# WS2812B_Ring_Light.net
KiCad netlist of a schematic drawn in Altium Designer
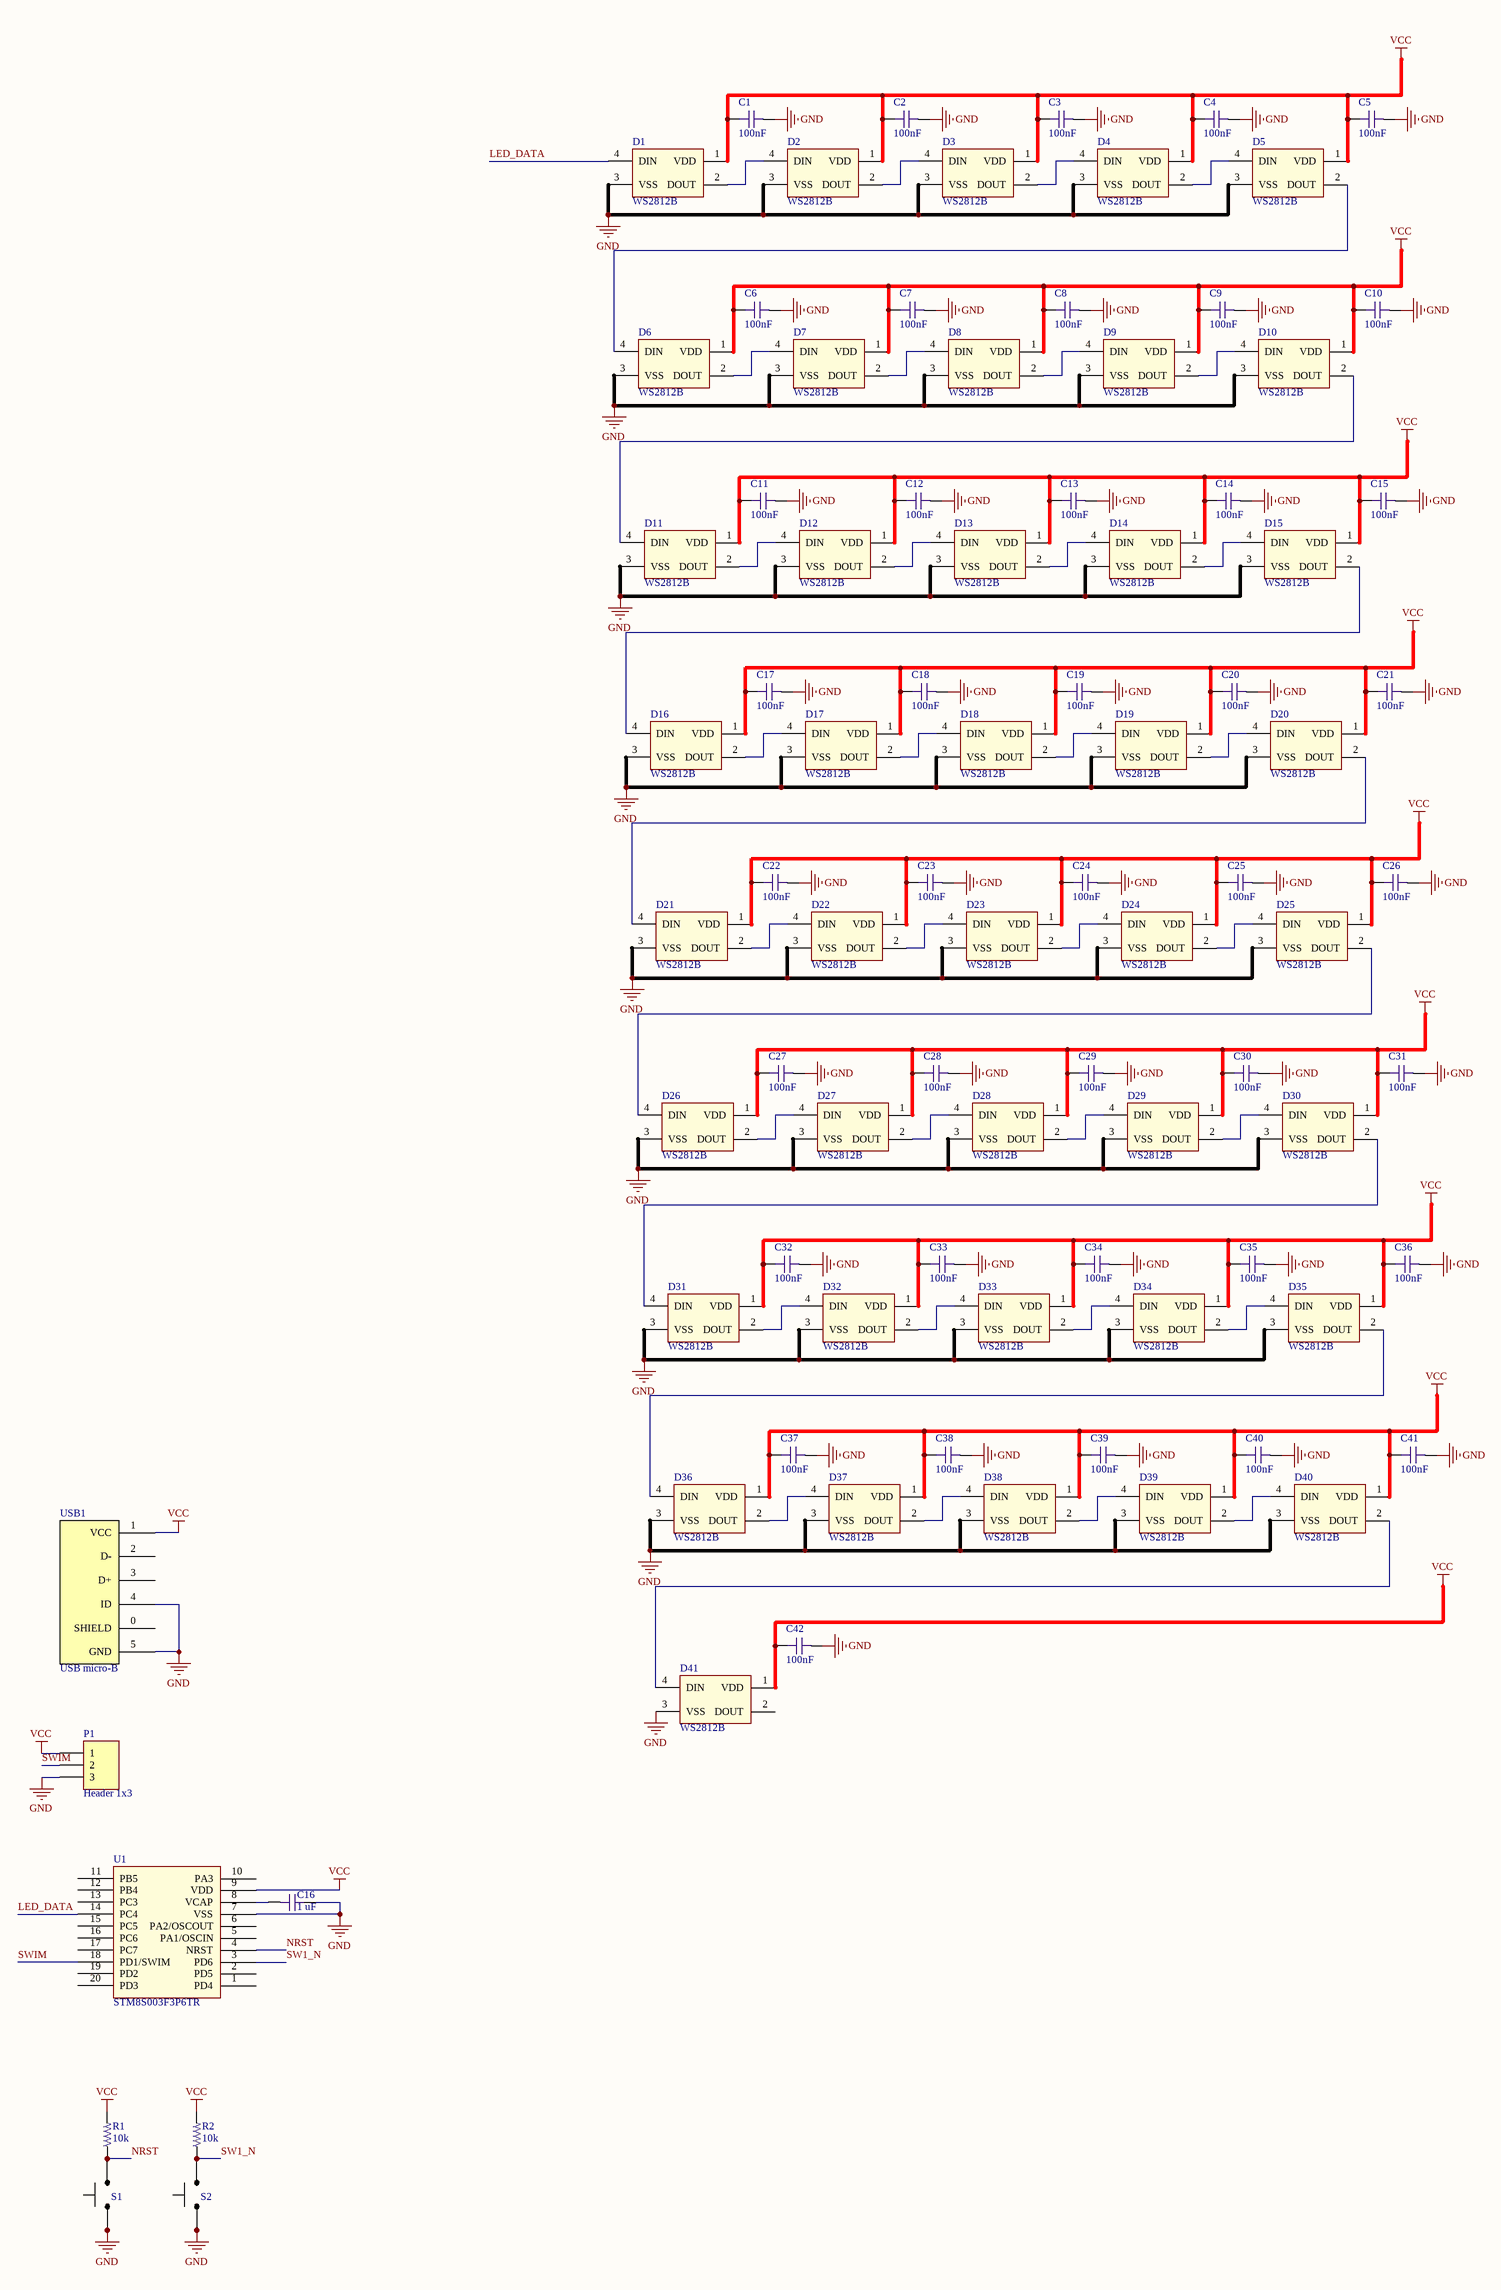
[diagram p0: WS2812B_Ring_Light.SchDoc]

(export (version "E")
  (design (tool "Eeschema 10.0.6"))
  (components
    (comp (ref "C1")
      (value "100nF")
      (footprint "C0603-IPC")
      (description "Chip Capacitor, 0603, 100nF, 25V, X7R")
      (fields (field (name "Comment") "C0603 100nF 25V X7R"))
      (libsource (lib "Capacitors") (part "C0603 100nF 25V X7R"))
    )
    (comp (ref "C2")
      (value "100nF")
      (footprint "C0603-IPC")
      (description "Chip Capacitor, 0603, 100nF, 25V, X7R")
      (fields (field (name "Comment") "C0603 100nF 25V X7R"))
      (libsource (lib "Capacitors") (part "C0603 100nF 25V X7R"))
    )
    (comp (ref "C3")
      (value "100nF")
      (footprint "C0603-IPC")
      (description "Chip Capacitor, 0603, 100nF, 25V, X7R")
      (fields (field (name "Comment") "C0603 100nF 25V X7R"))
      (libsource (lib "Capacitors") (part "C0603 100nF 25V X7R"))
    )
    (comp (ref "C4")
      (value "100nF")
      (footprint "C0603-IPC")
      (description "Chip Capacitor, 0603, 100nF, 25V, X7R")
      (fields (field (name "Comment") "C0603 100nF 25V X7R"))
      (libsource (lib "Capacitors") (part "C0603 100nF 25V X7R"))
    )
    (comp (ref "C5")
      (value "100nF")
      (footprint "C0603-IPC")
      (description "Chip Capacitor, 0603, 100nF, 25V, X7R")
      (fields (field (name "Comment") "C0603 100nF 25V X7R"))
      (libsource (lib "Capacitors") (part "C0603 100nF 25V X7R"))
    )
    (comp (ref "C6")
      (value "100nF")
      (footprint "C0603-IPC")
      (description "Chip Capacitor, 0603, 100nF, 25V, X7R")
      (fields (field (name "Comment") "C0603 100nF 25V X7R"))
      (libsource (lib "Capacitors") (part "C0603 100nF 25V X7R"))
    )
    (comp (ref "C7")
      (value "100nF")
      (footprint "C0603-IPC")
      (description "Chip Capacitor, 0603, 100nF, 25V, X7R")
      (fields (field (name "Comment") "C0603 100nF 25V X7R"))
      (libsource (lib "Capacitors") (part "C0603 100nF 25V X7R"))
    )
    (comp (ref "C8")
      (value "100nF")
      (footprint "C0603-IPC")
      (description "Chip Capacitor, 0603, 100nF, 25V, X7R")
      (fields (field (name "Comment") "C0603 100nF 25V X7R"))
      (libsource (lib "Capacitors") (part "C0603 100nF 25V X7R"))
    )
    (comp (ref "C9")
      (value "100nF")
      (footprint "C0603-IPC")
      (description "Chip Capacitor, 0603, 100nF, 25V, X7R")
      (fields (field (name "Comment") "C0603 100nF 25V X7R"))
      (libsource (lib "Capacitors") (part "C0603 100nF 25V X7R"))
    )
    (comp (ref "C10")
      (value "100nF")
      (footprint "C0603-IPC")
      (description "Chip Capacitor, 0603, 100nF, 25V, X7R")
      (fields (field (name "Comment") "C0603 100nF 25V X7R"))
      (libsource (lib "Capacitors") (part "C0603 100nF 25V X7R"))
    )
    (comp (ref "C11")
      (value "100nF")
      (footprint "C0603-IPC")
      (description "Chip Capacitor, 0603, 100nF, 25V, X7R")
      (fields (field (name "Comment") "C0603 100nF 25V X7R"))
      (libsource (lib "Capacitors") (part "C0603 100nF 25V X7R"))
    )
    (comp (ref "C12")
      (value "100nF")
      (footprint "C0603-IPC")
      (description "Chip Capacitor, 0603, 100nF, 25V, X7R")
      (fields (field (name "Comment") "C0603 100nF 25V X7R"))
      (libsource (lib "Capacitors") (part "C0603 100nF 25V X7R"))
    )
    (comp (ref "C13")
      (value "100nF")
      (footprint "C0603-IPC")
      (description "Chip Capacitor, 0603, 100nF, 25V, X7R")
      (fields (field (name "Comment") "C0603 100nF 25V X7R"))
      (libsource (lib "Capacitors") (part "C0603 100nF 25V X7R"))
    )
    (comp (ref "C14")
      (value "100nF")
      (footprint "C0603-IPC")
      (description "Chip Capacitor, 0603, 100nF, 25V, X7R")
      (fields (field (name "Comment") "C0603 100nF 25V X7R"))
      (libsource (lib "Capacitors") (part "C0603 100nF 25V X7R"))
    )
    (comp (ref "C15")
      (value "100nF")
      (footprint "C0603-IPC")
      (description "Chip Capacitor, 0603, 100nF, 25V, X7R")
      (fields (field (name "Comment") "C0603 100nF 25V X7R"))
      (libsource (lib "Capacitors") (part "C0603 100nF 25V X7R"))
    )
    (comp (ref "C16")
      (value "1 uF")
      (footprint "C0603-IPC")
      (description "Chip Capacitor, 0603, 1uF +/- 0.1uF, 10V, X7R")
      (fields (field (name "Comment") "C0603 1uF 10V X7R"))
      (libsource (lib "Capacitors") (part "C0603 1uF 10V X7R"))
    )
    (comp (ref "C17")
      (value "100nF")
      (footprint "C0603-IPC")
      (description "Chip Capacitor, 0603, 100nF, 25V, X7R")
      (fields (field (name "Comment") "C0603 100nF 25V X7R"))
      (libsource (lib "Capacitors") (part "C0603 100nF 25V X7R"))
    )
    (comp (ref "C18")
      (value "100nF")
      (footprint "C0603-IPC")
      (description "Chip Capacitor, 0603, 100nF, 25V, X7R")
      (fields (field (name "Comment") "C0603 100nF 25V X7R"))
      (libsource (lib "Capacitors") (part "C0603 100nF 25V X7R"))
    )
    (comp (ref "C19")
      (value "100nF")
      (footprint "C0603-IPC")
      (description "Chip Capacitor, 0603, 100nF, 25V, X7R")
      (fields (field (name "Comment") "C0603 100nF 25V X7R"))
      (libsource (lib "Capacitors") (part "C0603 100nF 25V X7R"))
    )
    (comp (ref "C20")
      (value "100nF")
      (footprint "C0603-IPC")
      (description "Chip Capacitor, 0603, 100nF, 25V, X7R")
      (fields (field (name "Comment") "C0603 100nF 25V X7R"))
      (libsource (lib "Capacitors") (part "C0603 100nF 25V X7R"))
    )
    (comp (ref "C21")
      (value "100nF")
      (footprint "C0603-IPC")
      (description "Chip Capacitor, 0603, 100nF, 25V, X7R")
      (fields (field (name "Comment") "C0603 100nF 25V X7R"))
      (libsource (lib "Capacitors") (part "C0603 100nF 25V X7R"))
    )
    (comp (ref "C22")
      (value "100nF")
      (footprint "C0603-IPC")
      (description "Chip Capacitor, 0603, 100nF, 25V, X7R")
      (fields (field (name "Comment") "C0603 100nF 25V X7R"))
      (libsource (lib "Capacitors") (part "C0603 100nF 25V X7R"))
    )
    (comp (ref "C23")
      (value "100nF")
      (footprint "C0603-IPC")
      (description "Chip Capacitor, 0603, 100nF, 25V, X7R")
      (fields (field (name "Comment") "C0603 100nF 25V X7R"))
      (libsource (lib "Capacitors") (part "C0603 100nF 25V X7R"))
    )
    (comp (ref "C24")
      (value "100nF")
      (footprint "C0603-IPC")
      (description "Chip Capacitor, 0603, 100nF, 25V, X7R")
      (fields (field (name "Comment") "C0603 100nF 25V X7R"))
      (libsource (lib "Capacitors") (part "C0603 100nF 25V X7R"))
    )
    (comp (ref "C25")
      (value "100nF")
      (footprint "C0603-IPC")
      (description "Chip Capacitor, 0603, 100nF, 25V, X7R")
      (fields (field (name "Comment") "C0603 100nF 25V X7R"))
      (libsource (lib "Capacitors") (part "C0603 100nF 25V X7R"))
    )
    (comp (ref "C26")
      (value "100nF")
      (footprint "C0603-IPC")
      (description "Chip Capacitor, 0603, 100nF, 25V, X7R")
      (fields (field (name "Comment") "C0603 100nF 25V X7R"))
      (libsource (lib "Capacitors") (part "C0603 100nF 25V X7R"))
    )
    (comp (ref "C27")
      (value "100nF")
      (footprint "C0603-IPC")
      (description "Chip Capacitor, 0603, 100nF, 25V, X7R")
      (fields (field (name "Comment") "C0603 100nF 25V X7R"))
      (libsource (lib "Capacitors") (part "C0603 100nF 25V X7R"))
    )
    (comp (ref "C28")
      (value "100nF")
      (footprint "C0603-IPC")
      (description "Chip Capacitor, 0603, 100nF, 25V, X7R")
      (fields (field (name "Comment") "C0603 100nF 25V X7R"))
      (libsource (lib "Capacitors") (part "C0603 100nF 25V X7R"))
    )
    (comp (ref "C29")
      (value "100nF")
      (footprint "C0603-IPC")
      (description "Chip Capacitor, 0603, 100nF, 25V, X7R")
      (fields (field (name "Comment") "C0603 100nF 25V X7R"))
      (libsource (lib "Capacitors") (part "C0603 100nF 25V X7R"))
    )
    (comp (ref "C30")
      (value "100nF")
      (footprint "C0603-IPC")
      (description "Chip Capacitor, 0603, 100nF, 25V, X7R")
      (fields (field (name "Comment") "C0603 100nF 25V X7R"))
      (libsource (lib "Capacitors") (part "C0603 100nF 25V X7R"))
    )
    (comp (ref "C31")
      (value "100nF")
      (footprint "C0603-IPC")
      (description "Chip Capacitor, 0603, 100nF, 25V, X7R")
      (fields (field (name "Comment") "C0603 100nF 25V X7R"))
      (libsource (lib "Capacitors") (part "C0603 100nF 25V X7R"))
    )
    (comp (ref "C32")
      (value "100nF")
      (footprint "C0603-IPC")
      (description "Chip Capacitor, 0603, 100nF, 25V, X7R")
      (fields (field (name "Comment") "C0603 100nF 25V X7R"))
      (libsource (lib "Capacitors") (part "C0603 100nF 25V X7R"))
    )
    (comp (ref "C33")
      (value "100nF")
      (footprint "C0603-IPC")
      (description "Chip Capacitor, 0603, 100nF, 25V, X7R")
      (fields (field (name "Comment") "C0603 100nF 25V X7R"))
      (libsource (lib "Capacitors") (part "C0603 100nF 25V X7R"))
    )
    (comp (ref "C34")
      (value "100nF")
      (footprint "C0603-IPC")
      (description "Chip Capacitor, 0603, 100nF, 25V, X7R")
      (fields (field (name "Comment") "C0603 100nF 25V X7R"))
      (libsource (lib "Capacitors") (part "C0603 100nF 25V X7R"))
    )
    (comp (ref "C35")
      (value "100nF")
      (footprint "C0603-IPC")
      (description "Chip Capacitor, 0603, 100nF, 25V, X7R")
      (fields (field (name "Comment") "C0603 100nF 25V X7R"))
      (libsource (lib "Capacitors") (part "C0603 100nF 25V X7R"))
    )
    (comp (ref "C36")
      (value "100nF")
      (footprint "C0603-IPC")
      (description "Chip Capacitor, 0603, 100nF, 25V, X7R")
      (fields (field (name "Comment") "C0603 100nF 25V X7R"))
      (libsource (lib "Capacitors") (part "C0603 100nF 25V X7R"))
    )
    (comp (ref "C37")
      (value "100nF")
      (footprint "C0603-IPC")
      (description "Chip Capacitor, 0603, 100nF, 25V, X7R")
      (fields (field (name "Comment") "C0603 100nF 25V X7R"))
      (libsource (lib "Capacitors") (part "C0603 100nF 25V X7R"))
    )
    (comp (ref "C38")
      (value "100nF")
      (footprint "C0603-IPC")
      (description "Chip Capacitor, 0603, 100nF, 25V, X7R")
      (fields (field (name "Comment") "C0603 100nF 25V X7R"))
      (libsource (lib "Capacitors") (part "C0603 100nF 25V X7R"))
    )
    (comp (ref "C39")
      (value "100nF")
      (footprint "C0603-IPC")
      (description "Chip Capacitor, 0603, 100nF, 25V, X7R")
      (fields (field (name "Comment") "C0603 100nF 25V X7R"))
      (libsource (lib "Capacitors") (part "C0603 100nF 25V X7R"))
    )
    (comp (ref "C40")
      (value "100nF")
      (footprint "C0603-IPC")
      (description "Chip Capacitor, 0603, 100nF, 25V, X7R")
      (fields (field (name "Comment") "C0603 100nF 25V X7R"))
      (libsource (lib "Capacitors") (part "C0603 100nF 25V X7R"))
    )
    (comp (ref "C41")
      (value "100nF")
      (footprint "C0603-IPC")
      (description "Chip Capacitor, 0603, 100nF, 25V, X7R")
      (fields (field (name "Comment") "C0603 100nF 25V X7R"))
      (libsource (lib "Capacitors") (part "C0603 100nF 25V X7R"))
    )
    (comp (ref "C42")
      (value "100nF")
      (footprint "C0603-IPC")
      (description "Chip Capacitor, 0603, 100nF, 25V, X7R")
      (fields (field (name "Comment") "C0603 100nF 25V X7R"))
      (libsource (lib "Capacitors") (part "C0603 100nF 25V X7R"))
    )
    (comp (ref "D1")
      (value "WS2812B")
      (footprint "WS2812B")
      (description "Addressable Lighting - Discrete Serial Red, Green, Blue (RGB) 5.00mm L x 5.00mm WS2812B")
      (libsource (lib "Diodes") (part "WS2812B"))
    )
    (comp (ref "D2")
      (value "WS2812B")
      (footprint "WS2812B")
      (description "Addressable Lighting - Discrete Serial Red, Green, Blue (RGB) 5.00mm L x 5.00mm WS2812B")
      (libsource (lib "Diodes") (part "WS2812B"))
    )
    (comp (ref "D3")
      (value "WS2812B")
      (footprint "WS2812B")
      (description "Addressable Lighting - Discrete Serial Red, Green, Blue (RGB) 5.00mm L x 5.00mm WS2812B")
      (libsource (lib "Diodes") (part "WS2812B"))
    )
    (comp (ref "D4")
      (value "WS2812B")
      (footprint "WS2812B")
      (description "Addressable Lighting - Discrete Serial Red, Green, Blue (RGB) 5.00mm L x 5.00mm WS2812B")
      (libsource (lib "Diodes") (part "WS2812B"))
    )
    (comp (ref "D5")
      (value "WS2812B")
      (footprint "WS2812B")
      (description "Addressable Lighting - Discrete Serial Red, Green, Blue (RGB) 5.00mm L x 5.00mm WS2812B")
      (libsource (lib "Diodes") (part "WS2812B"))
    )
    (comp (ref "D6")
      (value "WS2812B")
      (footprint "WS2812B")
      (description "Addressable Lighting - Discrete Serial Red, Green, Blue (RGB) 5.00mm L x 5.00mm WS2812B")
      (libsource (lib "Diodes") (part "WS2812B"))
    )
    (comp (ref "D7")
      (value "WS2812B")
      (footprint "WS2812B")
      (description "Addressable Lighting - Discrete Serial Red, Green, Blue (RGB) 5.00mm L x 5.00mm WS2812B")
      (libsource (lib "Diodes") (part "WS2812B"))
    )
    (comp (ref "D8")
      (value "WS2812B")
      (footprint "WS2812B")
      (description "Addressable Lighting - Discrete Serial Red, Green, Blue (RGB) 5.00mm L x 5.00mm WS2812B")
      (libsource (lib "Diodes") (part "WS2812B"))
    )
    (comp (ref "D9")
      (value "WS2812B")
      (footprint "WS2812B")
      (description "Addressable Lighting - Discrete Serial Red, Green, Blue (RGB) 5.00mm L x 5.00mm WS2812B")
      (libsource (lib "Diodes") (part "WS2812B"))
    )
    (comp (ref "D10")
      (value "WS2812B")
      (footprint "WS2812B")
      (description "Addressable Lighting - Discrete Serial Red, Green, Blue (RGB) 5.00mm L x 5.00mm WS2812B")
      (libsource (lib "Diodes") (part "WS2812B"))
    )
    (comp (ref "D11")
      (value "WS2812B")
      (footprint "WS2812B")
      (description "Addressable Lighting - Discrete Serial Red, Green, Blue (RGB) 5.00mm L x 5.00mm WS2812B")
      (libsource (lib "Diodes") (part "WS2812B"))
    )
    (comp (ref "D12")
      (value "WS2812B")
      (footprint "WS2812B")
      (description "Addressable Lighting - Discrete Serial Red, Green, Blue (RGB) 5.00mm L x 5.00mm WS2812B")
      (libsource (lib "Diodes") (part "WS2812B"))
    )
    (comp (ref "D13")
      (value "WS2812B")
      (footprint "WS2812B")
      (description "Addressable Lighting - Discrete Serial Red, Green, Blue (RGB) 5.00mm L x 5.00mm WS2812B")
      (libsource (lib "Diodes") (part "WS2812B"))
    )
    (comp (ref "D14")
      (value "WS2812B")
      (footprint "WS2812B")
      (description "Addressable Lighting - Discrete Serial Red, Green, Blue (RGB) 5.00mm L x 5.00mm WS2812B")
      (libsource (lib "Diodes") (part "WS2812B"))
    )
    (comp (ref "D15")
      (value "WS2812B")
      (footprint "WS2812B")
      (description "Addressable Lighting - Discrete Serial Red, Green, Blue (RGB) 5.00mm L x 5.00mm WS2812B")
      (libsource (lib "Diodes") (part "WS2812B"))
    )
    (comp (ref "D16")
      (value "WS2812B")
      (footprint "WS2812B")
      (description "Addressable Lighting - Discrete Serial Red, Green, Blue (RGB) 5.00mm L x 5.00mm WS2812B")
      (libsource (lib "Diodes") (part "WS2812B"))
    )
    (comp (ref "D17")
      (value "WS2812B")
      (footprint "WS2812B")
      (description "Addressable Lighting - Discrete Serial Red, Green, Blue (RGB) 5.00mm L x 5.00mm WS2812B")
      (libsource (lib "Diodes") (part "WS2812B"))
    )
    (comp (ref "D18")
      (value "WS2812B")
      (footprint "WS2812B")
      (description "Addressable Lighting - Discrete Serial Red, Green, Blue (RGB) 5.00mm L x 5.00mm WS2812B")
      (libsource (lib "Diodes") (part "WS2812B"))
    )
    (comp (ref "D19")
      (value "WS2812B")
      (footprint "WS2812B")
      (description "Addressable Lighting - Discrete Serial Red, Green, Blue (RGB) 5.00mm L x 5.00mm WS2812B")
      (libsource (lib "Diodes") (part "WS2812B"))
    )
    (comp (ref "D20")
      (value "WS2812B")
      (footprint "WS2812B")
      (description "Addressable Lighting - Discrete Serial Red, Green, Blue (RGB) 5.00mm L x 5.00mm WS2812B")
      (libsource (lib "Diodes") (part "WS2812B"))
    )
    (comp (ref "D21")
      (value "WS2812B")
      (footprint "WS2812B")
      (description "Addressable Lighting - Discrete Serial Red, Green, Blue (RGB) 5.00mm L x 5.00mm WS2812B")
      (libsource (lib "Diodes") (part "WS2812B"))
    )
    (comp (ref "D22")
      (value "WS2812B")
      (footprint "WS2812B")
      (description "Addressable Lighting - Discrete Serial Red, Green, Blue (RGB) 5.00mm L x 5.00mm WS2812B")
      (libsource (lib "Diodes") (part "WS2812B"))
    )
    (comp (ref "D23")
      (value "WS2812B")
      (footprint "WS2812B")
      (description "Addressable Lighting - Discrete Serial Red, Green, Blue (RGB) 5.00mm L x 5.00mm WS2812B")
      (libsource (lib "Diodes") (part "WS2812B"))
    )
    (comp (ref "D24")
      (value "WS2812B")
      (footprint "WS2812B")
      (description "Addressable Lighting - Discrete Serial Red, Green, Blue (RGB) 5.00mm L x 5.00mm WS2812B")
      (libsource (lib "Diodes") (part "WS2812B"))
    )
    (comp (ref "D25")
      (value "WS2812B")
      (footprint "WS2812B")
      (description "Addressable Lighting - Discrete Serial Red, Green, Blue (RGB) 5.00mm L x 5.00mm WS2812B")
      (libsource (lib "Diodes") (part "WS2812B"))
    )
    (comp (ref "D26")
      (value "WS2812B")
      (footprint "WS2812B")
      (description "Addressable Lighting - Discrete Serial Red, Green, Blue (RGB) 5.00mm L x 5.00mm WS2812B")
      (libsource (lib "Diodes") (part "WS2812B"))
    )
    (comp (ref "D27")
      (value "WS2812B")
      (footprint "WS2812B")
      (description "Addressable Lighting - Discrete Serial Red, Green, Blue (RGB) 5.00mm L x 5.00mm WS2812B")
      (libsource (lib "Diodes") (part "WS2812B"))
    )
    (comp (ref "D28")
      (value "WS2812B")
      (footprint "WS2812B")
      (description "Addressable Lighting - Discrete Serial Red, Green, Blue (RGB) 5.00mm L x 5.00mm WS2812B")
      (libsource (lib "Diodes") (part "WS2812B"))
    )
    (comp (ref "D29")
      (value "WS2812B")
      (footprint "WS2812B")
      (description "Addressable Lighting - Discrete Serial Red, Green, Blue (RGB) 5.00mm L x 5.00mm WS2812B")
      (libsource (lib "Diodes") (part "WS2812B"))
    )
    (comp (ref "D30")
      (value "WS2812B")
      (footprint "WS2812B")
      (description "Addressable Lighting - Discrete Serial Red, Green, Blue (RGB) 5.00mm L x 5.00mm WS2812B")
      (libsource (lib "Diodes") (part "WS2812B"))
    )
    (comp (ref "D31")
      (value "WS2812B")
      (footprint "WS2812B")
      (description "Addressable Lighting - Discrete Serial Red, Green, Blue (RGB) 5.00mm L x 5.00mm WS2812B")
      (libsource (lib "Diodes") (part "WS2812B"))
    )
    (comp (ref "D32")
      (value "WS2812B")
      (footprint "WS2812B")
      (description "Addressable Lighting - Discrete Serial Red, Green, Blue (RGB) 5.00mm L x 5.00mm WS2812B")
      (libsource (lib "Diodes") (part "WS2812B"))
    )
    (comp (ref "D33")
      (value "WS2812B")
      (footprint "WS2812B")
      (description "Addressable Lighting - Discrete Serial Red, Green, Blue (RGB) 5.00mm L x 5.00mm WS2812B")
      (libsource (lib "Diodes") (part "WS2812B"))
    )
    (comp (ref "D34")
      (value "WS2812B")
      (footprint "WS2812B")
      (description "Addressable Lighting - Discrete Serial Red, Green, Blue (RGB) 5.00mm L x 5.00mm WS2812B")
      (libsource (lib "Diodes") (part "WS2812B"))
    )
    (comp (ref "D35")
      (value "WS2812B")
      (footprint "WS2812B")
      (description "Addressable Lighting - Discrete Serial Red, Green, Blue (RGB) 5.00mm L x 5.00mm WS2812B")
      (libsource (lib "Diodes") (part "WS2812B"))
    )
    (comp (ref "D36")
      (value "WS2812B")
      (footprint "WS2812B")
      (description "Addressable Lighting - Discrete Serial Red, Green, Blue (RGB) 5.00mm L x 5.00mm WS2812B")
      (libsource (lib "Diodes") (part "WS2812B"))
    )
    (comp (ref "D37")
      (value "WS2812B")
      (footprint "WS2812B")
      (description "Addressable Lighting - Discrete Serial Red, Green, Blue (RGB) 5.00mm L x 5.00mm WS2812B")
      (libsource (lib "Diodes") (part "WS2812B"))
    )
    (comp (ref "D38")
      (value "WS2812B")
      (footprint "WS2812B")
      (description "Addressable Lighting - Discrete Serial Red, Green, Blue (RGB) 5.00mm L x 5.00mm WS2812B")
      (libsource (lib "Diodes") (part "WS2812B"))
    )
    (comp (ref "D39")
      (value "WS2812B")
      (footprint "WS2812B")
      (description "Addressable Lighting - Discrete Serial Red, Green, Blue (RGB) 5.00mm L x 5.00mm WS2812B")
      (libsource (lib "Diodes") (part "WS2812B"))
    )
    (comp (ref "D40")
      (value "WS2812B")
      (footprint "WS2812B")
      (description "Addressable Lighting - Discrete Serial Red, Green, Blue (RGB) 5.00mm L x 5.00mm WS2812B")
      (libsource (lib "Diodes") (part "WS2812B"))
    )
    (comp (ref "D41")
      (value "WS2812B")
      (footprint "WS2812B")
      (description "Addressable Lighting - Discrete Serial Red, Green, Blue (RGB) 5.00mm L x 5.00mm WS2812B")
      (libsource (lib "Diodes") (part "WS2812B"))
    )
    (comp (ref "P1")
      (value "Header 1x3")
      (footprint "HEADER 1X3 SMD 2.54mm")
      (description "Header, 3-Pin")
      (fields (field (name "PUBLISHER") "Altium Limited"))
      (libsource (lib "Connectors") (part "Header 1x3"))
    )
    (comp (ref "R1")
      (value "10k")
      (footprint "R0603-IPC")
      (description "RES SMD 10K OHM 1% 1/10W 0603")
      (fields (field (name "Comment") "R0603 10K 1%"))
      (libsource (lib "Resistors") (part "R0603 10K 1%"))
    )
    (comp (ref "R2")
      (value "10k")
      (footprint "R0603-IPC")
      (description "RES SMD 10K OHM 1% 1/10W 0603")
      (fields (field (name "Comment") "R0603 10K 1%"))
      (libsource (lib "Resistors") (part "R0603 10K 1%"))
    )
    (comp (ref "S1")
      (value "NRST")
      (footprint "TL3342F260QG")
      (description "SWITCH TACTILE SPST-NO 0.05A 12V")
      (fields (field (name "MANUFACTURER PART NUMBER") "TL3342F260QG"))
      (libsource (lib "Switches") (part "SWITCH TACTILE SPST"))
    )
    (comp (ref "S2")
      (value "USER")
      (footprint "TL3342F260QG")
      (description "SWITCH TACTILE SPST-NO 0.05A 12V")
      (fields (field (name "MANUFACTURER PART NUMBER") "TL3342F260QG"))
      (libsource (lib "Switches") (part "SWITCH TACTILE SPST"))
    )
    (comp (ref "U1")
      (value "STM8S003F3P6TR")
      (footprint "TSOP65P640X120-20N")
      (description "STM8 STM8S Microcontroller IC 8-Bit 16MHz 8KB (8K x 8) FLASH 20-TSSOP")
      (libsource (lib "Integrated Circuits") (part "STM8S003F3P6TR"))
    )
    (comp (ref "USB1")
      (value "USB micro-B")
      (footprint "USB-MicroB")
      (description "CONN RCPT USB TYPE B 3A")
      (fields
        (field (name "MANUFACTURER PART NUMBER") "629105150521")
        (field (name "MANUFACTURER") "Wurth Electronics Inc.")
      )
      (libsource (lib "Connectors") (part "USB micro-B"))
    )
  )
  (nets
    (net (code "1") (name "/LED_DATA") (class "Default")
      (node (ref "D1") (pin "4") (pinfunction "DIN_4") (pintype "passive"))
      (node (ref "U1") (pin "14") (pinfunction "PC4_14") (pintype "passive"))
    )
    (net (code "2") (name "/NRST") (class "Default")
      (node (ref "R1") (pin "1") (pintype "passive"))
      (node (ref "S1") (pin "1") (pinfunction "1_1") (pintype "passive"))
      (node (ref "S1") (pin "2") (pinfunction "2_2") (pintype "passive"))
      (node (ref "U1") (pin "4") (pinfunction "NRST_4") (pintype "passive"))
    )
    (net (code "3") (name "/SW1_N") (class "Default")
      (node (ref "R2") (pin "1") (pintype "passive"))
      (node (ref "S2") (pin "1") (pinfunction "1_1") (pintype "passive"))
      (node (ref "S2") (pin "2") (pinfunction "2_2") (pintype "passive"))
      (node (ref "U1") (pin "3") (pinfunction "PD6_3") (pintype "passive"))
    )
    (net (code "4") (name "/SWIM") (class "Default")
      (node (ref "P1") (pin "2") (pinfunction "2_2") (pintype "passive"))
      (node (ref "U1") (pin "18") (pinfunction "PD1/SWIM_18") (pintype "passive"))
    )
    (net (code "5") (name "GND") (class "Default")
      (node (ref "C1") (pin "1") (pintype "passive"))
      (node (ref "C10") (pin "1") (pintype "passive"))
      (node (ref "C11") (pin "1") (pintype "passive"))
      (node (ref "C12") (pin "1") (pintype "passive"))
      (node (ref "C13") (pin "1") (pintype "passive"))
      (node (ref "C14") (pin "1") (pintype "passive"))
      (node (ref "C15") (pin "1") (pintype "passive"))
      (node (ref "C16") (pin "2") (pintype "passive"))
      (node (ref "C17") (pin "1") (pintype "passive"))
      (node (ref "C18") (pin "1") (pintype "passive"))
      (node (ref "C19") (pin "1") (pintype "passive"))
      (node (ref "C2") (pin "1") (pintype "passive"))
      (node (ref "C20") (pin "1") (pintype "passive"))
      (node (ref "C21") (pin "1") (pintype "passive"))
      (node (ref "C22") (pin "1") (pintype "passive"))
      (node (ref "C23") (pin "1") (pintype "passive"))
      (node (ref "C24") (pin "1") (pintype "passive"))
      (node (ref "C25") (pin "1") (pintype "passive"))
      (node (ref "C26") (pin "1") (pintype "passive"))
      (node (ref "C27") (pin "1") (pintype "passive"))
      (node (ref "C28") (pin "1") (pintype "passive"))
      (node (ref "C29") (pin "1") (pintype "passive"))
      (node (ref "C3") (pin "1") (pintype "passive"))
      (node (ref "C30") (pin "1") (pintype "passive"))
      (node (ref "C31") (pin "1") (pintype "passive"))
      (node (ref "C32") (pin "1") (pintype "passive"))
      (node (ref "C33") (pin "1") (pintype "passive"))
      (node (ref "C34") (pin "1") (pintype "passive"))
      (node (ref "C35") (pin "1") (pintype "passive"))
      (node (ref "C36") (pin "1") (pintype "passive"))
      (node (ref "C37") (pin "1") (pintype "passive"))
      (node (ref "C38") (pin "1") (pintype "passive"))
      (node (ref "C39") (pin "1") (pintype "passive"))
      (node (ref "C4") (pin "1") (pintype "passive"))
      (node (ref "C40") (pin "1") (pintype "passive"))
      (node (ref "C41") (pin "1") (pintype "passive"))
      (node (ref "C42") (pin "1") (pintype "passive"))
      (node (ref "C5") (pin "1") (pintype "passive"))
      (node (ref "C6") (pin "1") (pintype "passive"))
      (node (ref "C7") (pin "1") (pintype "passive"))
      (node (ref "C8") (pin "1") (pintype "passive"))
      (node (ref "C9") (pin "1") (pintype "passive"))
      (node (ref "D1") (pin "3") (pinfunction "VSS_3") (pintype "passive"))
      (node (ref "D10") (pin "3") (pinfunction "VSS_3") (pintype "passive"))
      (node (ref "D11") (pin "3") (pinfunction "VSS_3") (pintype "passive"))
      (node (ref "D12") (pin "3") (pinfunction "VSS_3") (pintype "passive"))
      (node (ref "D13") (pin "3") (pinfunction "VSS_3") (pintype "passive"))
      (node (ref "D14") (pin "3") (pinfunction "VSS_3") (pintype "passive"))
      (node (ref "D15") (pin "3") (pinfunction "VSS_3") (pintype "passive"))
      (node (ref "D16") (pin "3") (pinfunction "VSS_3") (pintype "passive"))
      (node (ref "D17") (pin "3") (pinfunction "VSS_3") (pintype "passive"))
      (node (ref "D18") (pin "3") (pinfunction "VSS_3") (pintype "passive"))
      (node (ref "D19") (pin "3") (pinfunction "VSS_3") (pintype "passive"))
      (node (ref "D2") (pin "3") (pinfunction "VSS_3") (pintype "passive"))
      (node (ref "D20") (pin "3") (pinfunction "VSS_3") (pintype "passive"))
      (node (ref "D21") (pin "3") (pinfunction "VSS_3") (pintype "passive"))
      (node (ref "D22") (pin "3") (pinfunction "VSS_3") (pintype "passive"))
      (node (ref "D23") (pin "3") (pinfunction "VSS_3") (pintype "passive"))
      (node (ref "D24") (pin "3") (pinfunction "VSS_3") (pintype "passive"))
      (node (ref "D25") (pin "3") (pinfunction "VSS_3") (pintype "passive"))
      (node (ref "D26") (pin "3") (pinfunction "VSS_3") (pintype "passive"))
      (node (ref "D27") (pin "3") (pinfunction "VSS_3") (pintype "passive"))
      (node (ref "D28") (pin "3") (pinfunction "VSS_3") (pintype "passive"))
      (node (ref "D29") (pin "3") (pinfunction "VSS_3") (pintype "passive"))
      (node (ref "D3") (pin "3") (pinfunction "VSS_3") (pintype "passive"))
      (node (ref "D30") (pin "3") (pinfunction "VSS_3") (pintype "passive"))
      (node (ref "D31") (pin "3") (pinfunction "VSS_3") (pintype "passive"))
      (node (ref "D32") (pin "3") (pinfunction "VSS_3") (pintype "passive"))
      (node (ref "D33") (pin "3") (pinfunction "VSS_3") (pintype "passive"))
      (node (ref "D34") (pin "3") (pinfunction "VSS_3") (pintype "passive"))
      (node (ref "D35") (pin "3") (pinfunction "VSS_3") (pintype "passive"))
      (node (ref "D36") (pin "3") (pinfunction "VSS_3") (pintype "passive"))
      (node (ref "D37") (pin "3") (pinfunction "VSS_3") (pintype "passive"))
      (node (ref "D38") (pin "3") (pinfunction "VSS_3") (pintype "passive"))
      (node (ref "D39") (pin "3") (pinfunction "VSS_3") (pintype "passive"))
      (node (ref "D4") (pin "3") (pinfunction "VSS_3") (pintype "passive"))
      (node (ref "D40") (pin "3") (pinfunction "VSS_3") (pintype "passive"))
      (node (ref "D41") (pin "3") (pinfunction "VSS_3") (pintype "passive"))
      (node (ref "D5") (pin "3") (pinfunction "VSS_3") (pintype "passive"))
      (node (ref "D6") (pin "3") (pinfunction "VSS_3") (pintype "passive"))
      (node (ref "D7") (pin "3") (pinfunction "VSS_3") (pintype "passive"))
      (node (ref "D8") (pin "3") (pinfunction "VSS_3") (pintype "passive"))
      (node (ref "D9") (pin "3") (pinfunction "VSS_3") (pintype "passive"))
      (node (ref "P1") (pin "3") (pinfunction "3_3") (pintype "passive"))
      (node (ref "S1") (pin "3") (pinfunction "3_3") (pintype "passive"))
      (node (ref "S1") (pin "4") (pinfunction "4_4") (pintype "passive"))
      (node (ref "S2") (pin "3") (pinfunction "3_3") (pintype "passive"))
      (node (ref "S2") (pin "4") (pinfunction "4_4") (pintype "passive"))
      (node (ref "U1") (pin "7") (pinfunction "VSS_7") (pintype "passive"))
      (node (ref "USB1") (pin "4") (pinfunction "ID_4") (pintype "passive"))
      (node (ref "USB1") (pin "5") (pinfunction "GND_5") (pintype "passive"))
    )
    (net (code "6") (name "Net-(D1-DOUT)") (class "Default")
      (node (ref "D1") (pin "2") (pinfunction "DOUT_2") (pintype "passive"))
      (node (ref "D2") (pin "4") (pinfunction "DIN_4") (pintype "passive"))
    )
    (net (code "7") (name "Net-(D2-DOUT)") (class "Default")
      (node (ref "D2") (pin "2") (pinfunction "DOUT_2") (pintype "passive"))
      (node (ref "D3") (pin "4") (pinfunction "DIN_4") (pintype "passive"))
    )
    (net (code "8") (name "Net-(D3-DOUT)") (class "Default")
      (node (ref "D3") (pin "2") (pinfunction "DOUT_2") (pintype "passive"))
      (node (ref "D4") (pin "4") (pinfunction "DIN_4") (pintype "passive"))
    )
    (net (code "9") (name "Net-(D4-DOUT)") (class "Default")
      (node (ref "D4") (pin "2") (pinfunction "DOUT_2") (pintype "passive"))
      (node (ref "D5") (pin "4") (pinfunction "DIN_4") (pintype "passive"))
    )
    (net (code "10") (name "Net-(D5-DOUT)") (class "Default")
      (node (ref "D5") (pin "2") (pinfunction "DOUT_2") (pintype "passive"))
      (node (ref "D6") (pin "4") (pinfunction "DIN_4") (pintype "passive"))
    )
    (net (code "11") (name "Net-(D6-DOUT)") (class "Default")
      (node (ref "D6") (pin "2") (pinfunction "DOUT_2") (pintype "passive"))
      (node (ref "D7") (pin "4") (pinfunction "DIN_4") (pintype "passive"))
    )
    (net (code "12") (name "Net-(D7-DOUT)") (class "Default")
      (node (ref "D7") (pin "2") (pinfunction "DOUT_2") (pintype "passive"))
      (node (ref "D8") (pin "4") (pinfunction "DIN_4") (pintype "passive"))
    )
    (net (code "13") (name "Net-(D8-DOUT)") (class "Default")
      (node (ref "D8") (pin "2") (pinfunction "DOUT_2") (pintype "passive"))
      (node (ref "D9") (pin "4") (pinfunction "DIN_4") (pintype "passive"))
    )
    (net (code "14") (name "Net-(D10-DIN)") (class "Default")
      (node (ref "D10") (pin "4") (pinfunction "DIN_4") (pintype "passive"))
      (node (ref "D9") (pin "2") (pinfunction "DOUT_2") (pintype "passive"))
    )
    (net (code "15") (name "Net-(D10-DOUT)") (class "Default")
      (node (ref "D10") (pin "2") (pinfunction "DOUT_2") (pintype "passive"))
      (node (ref "D11") (pin "4") (pinfunction "DIN_4") (pintype "passive"))
    )
    (net (code "16") (name "Net-(D11-DOUT)") (class "Default")
      (node (ref "D11") (pin "2") (pinfunction "DOUT_2") (pintype "passive"))
      (node (ref "D12") (pin "4") (pinfunction "DIN_4") (pintype "passive"))
    )
    (net (code "17") (name "Net-(D12-DOUT)") (class "Default")
      (node (ref "D12") (pin "2") (pinfunction "DOUT_2") (pintype "passive"))
      (node (ref "D13") (pin "4") (pinfunction "DIN_4") (pintype "passive"))
    )
    (net (code "18") (name "Net-(D13-DOUT)") (class "Default")
      (node (ref "D13") (pin "2") (pinfunction "DOUT_2") (pintype "passive"))
      (node (ref "D14") (pin "4") (pinfunction "DIN_4") (pintype "passive"))
    )
    (net (code "19") (name "Net-(D14-DOUT)") (class "Default")
      (node (ref "D14") (pin "2") (pinfunction "DOUT_2") (pintype "passive"))
      (node (ref "D15") (pin "4") (pinfunction "DIN_4") (pintype "passive"))
    )
    (net (code "20") (name "Net-(D15-DOUT)") (class "Default")
      (node (ref "D15") (pin "2") (pinfunction "DOUT_2") (pintype "passive"))
      (node (ref "D16") (pin "4") (pinfunction "DIN_4") (pintype "passive"))
    )
    (net (code "21") (name "Net-(D16-DOUT)") (class "Default")
      (node (ref "D16") (pin "2") (pinfunction "DOUT_2") (pintype "passive"))
      (node (ref "D17") (pin "4") (pinfunction "DIN_4") (pintype "passive"))
    )
    (net (code "22") (name "Net-(D17-DOUT)") (class "Default")
      (node (ref "D17") (pin "2") (pinfunction "DOUT_2") (pintype "passive"))
      (node (ref "D18") (pin "4") (pinfunction "DIN_4") (pintype "passive"))
    )
    (net (code "23") (name "Net-(D18-DOUT)") (class "Default")
      (node (ref "D18") (pin "2") (pinfunction "DOUT_2") (pintype "passive"))
      (node (ref "D19") (pin "4") (pinfunction "DIN_4") (pintype "passive"))
    )
    (net (code "24") (name "Net-(D19-DOUT)") (class "Default")
      (node (ref "D19") (pin "2") (pinfunction "DOUT_2") (pintype "passive"))
      (node (ref "D20") (pin "4") (pinfunction "DIN_4") (pintype "passive"))
    )
    (net (code "25") (name "Net-(D20-DOUT)") (class "Default")
      (node (ref "D20") (pin "2") (pinfunction "DOUT_2") (pintype "passive"))
      (node (ref "D21") (pin "4") (pinfunction "DIN_4") (pintype "passive"))
    )
    (net (code "26") (name "Net-(D21-DOUT)") (class "Default")
      (node (ref "D21") (pin "2") (pinfunction "DOUT_2") (pintype "passive"))
      (node (ref "D22") (pin "4") (pinfunction "DIN_4") (pintype "passive"))
    )
    (net (code "27") (name "Net-(D22-DOUT)") (class "Default")
      (node (ref "D22") (pin "2") (pinfunction "DOUT_2") (pintype "passive"))
      (node (ref "D23") (pin "4") (pinfunction "DIN_4") (pintype "passive"))
    )
    (net (code "28") (name "Net-(D23-DOUT)") (class "Default")
      (node (ref "D23") (pin "2") (pinfunction "DOUT_2") (pintype "passive"))
      (node (ref "D24") (pin "4") (pinfunction "DIN_4") (pintype "passive"))
    )
    (net (code "29") (name "Net-(D24-DOUT)") (class "Default")
      (node (ref "D24") (pin "2") (pinfunction "DOUT_2") (pintype "passive"))
      (node (ref "D25") (pin "4") (pinfunction "DIN_4") (pintype "passive"))
    )
    (net (code "30") (name "Net-(D25-DOUT)") (class "Default")
      (node (ref "D25") (pin "2") (pinfunction "DOUT_2") (pintype "passive"))
      (node (ref "D26") (pin "4") (pinfunction "DIN_4") (pintype "passive"))
    )
    (net (code "31") (name "Net-(D26-DOUT)") (class "Default")
      (node (ref "D26") (pin "2") (pinfunction "DOUT_2") (pintype "passive"))
      (node (ref "D27") (pin "4") (pinfunction "DIN_4") (pintype "passive"))
    )
    (net (code "32") (name "Net-(D27-DOUT)") (class "Default")
      (node (ref "D27") (pin "2") (pinfunction "DOUT_2") (pintype "passive"))
      (node (ref "D28") (pin "4") (pinfunction "DIN_4") (pintype "passive"))
    )
    (net (code "33") (name "Net-(D28-DOUT)") (class "Default")
      (node (ref "D28") (pin "2") (pinfunction "DOUT_2") (pintype "passive"))
      (node (ref "D29") (pin "4") (pinfunction "DIN_4") (pintype "passive"))
    )
    (net (code "34") (name "Net-(D29-DOUT)") (class "Default")
      (node (ref "D29") (pin "2") (pinfunction "DOUT_2") (pintype "passive"))
      (node (ref "D30") (pin "4") (pinfunction "DIN_4") (pintype "passive"))
    )
    (net (code "35") (name "Net-(D30-DOUT)") (class "Default")
      (node (ref "D30") (pin "2") (pinfunction "DOUT_2") (pintype "passive"))
      (node (ref "D31") (pin "4") (pinfunction "DIN_4") (pintype "passive"))
    )
    (net (code "36") (name "Net-(D31-DOUT)") (class "Default")
      (node (ref "D31") (pin "2") (pinfunction "DOUT_2") (pintype "passive"))
      (node (ref "D32") (pin "4") (pinfunction "DIN_4") (pintype "passive"))
    )
    (net (code "37") (name "Net-(D32-DOUT)") (class "Default")
      (node (ref "D32") (pin "2") (pinfunction "DOUT_2") (pintype "passive"))
      (node (ref "D33") (pin "4") (pinfunction "DIN_4") (pintype "passive"))
    )
    (net (code "38") (name "Net-(D33-DOUT)") (class "Default")
      (node (ref "D33") (pin "2") (pinfunction "DOUT_2") (pintype "passive"))
      (node (ref "D34") (pin "4") (pinfunction "DIN_4") (pintype "passive"))
    )
    (net (code "39") (name "Net-(D34-DOUT)") (class "Default")
      (node (ref "D34") (pin "2") (pinfunction "DOUT_2") (pintype "passive"))
      (node (ref "D35") (pin "4") (pinfunction "DIN_4") (pintype "passive"))
    )
    (net (code "40") (name "Net-(D35-DOUT)") (class "Default")
      (node (ref "D35") (pin "2") (pinfunction "DOUT_2") (pintype "passive"))
      (node (ref "D36") (pin "4") (pinfunction "DIN_4") (pintype "passive"))
    )
    (net (code "41") (name "Net-(D36-DOUT)") (class "Default")
      (node (ref "D36") (pin "2") (pinfunction "DOUT_2") (pintype "passive"))
      (node (ref "D37") (pin "4") (pinfunction "DIN_4") (pintype "passive"))
    )
    (net (code "42") (name "Net-(D37-DOUT)") (class "Default")
      (node (ref "D37") (pin "2") (pinfunction "DOUT_2") (pintype "passive"))
      (node (ref "D38") (pin "4") (pinfunction "DIN_4") (pintype "passive"))
    )
    (net (code "43") (name "Net-(D38-DOUT)") (class "Default")
      (node (ref "D38") (pin "2") (pinfunction "DOUT_2") (pintype "passive"))
      (node (ref "D39") (pin "4") (pinfunction "DIN_4") (pintype "passive"))
    )
    (net (code "44") (name "Net-(D39-DOUT)") (class "Default")
      (node (ref "D39") (pin "2") (pinfunction "DOUT_2") (pintype "passive"))
      (node (ref "D40") (pin "4") (pinfunction "DIN_4") (pintype "passive"))
    )
    (net (code "45") (name "Net-(D40-DOUT)") (class "Default")
      (node (ref "D40") (pin "2") (pinfunction "DOUT_2") (pintype "passive"))
      (node (ref "D41") (pin "4") (pinfunction "DIN_4") (pintype "passive"))
    )
    (net (code "46") (name "Net-(U1-VCAP)") (class "Default")
      (node (ref "C16") (pin "1") (pintype "passive"))
      (node (ref "U1") (pin "8") (pinfunction "VCAP_8") (pintype "passive"))
    )
    (net (code "47") (name "VCC") (class "Default")
      (node (ref "C1") (pin "2") (pintype "passive"))
      (node (ref "C10") (pin "2") (pintype "passive"))
      (node (ref "C11") (pin "2") (pintype "passive"))
      (node (ref "C12") (pin "2") (pintype "passive"))
      (node (ref "C13") (pin "2") (pintype "passive"))
      (node (ref "C14") (pin "2") (pintype "passive"))
      (node (ref "C15") (pin "2") (pintype "passive"))
      (node (ref "C17") (pin "2") (pintype "passive"))
      (node (ref "C18") (pin "2") (pintype "passive"))
      (node (ref "C19") (pin "2") (pintype "passive"))
      (node (ref "C2") (pin "2") (pintype "passive"))
      (node (ref "C20") (pin "2") (pintype "passive"))
      (node (ref "C21") (pin "2") (pintype "passive"))
      (node (ref "C22") (pin "2") (pintype "passive"))
      (node (ref "C23") (pin "2") (pintype "passive"))
      (node (ref "C24") (pin "2") (pintype "passive"))
      (node (ref "C25") (pin "2") (pintype "passive"))
      (node (ref "C26") (pin "2") (pintype "passive"))
      (node (ref "C27") (pin "2") (pintype "passive"))
      (node (ref "C28") (pin "2") (pintype "passive"))
      (node (ref "C29") (pin "2") (pintype "passive"))
      (node (ref "C3") (pin "2") (pintype "passive"))
      (node (ref "C30") (pin "2") (pintype "passive"))
      (node (ref "C31") (pin "2") (pintype "passive"))
      (node (ref "C32") (pin "2") (pintype "passive"))
      (node (ref "C33") (pin "2") (pintype "passive"))
      (node (ref "C34") (pin "2") (pintype "passive"))
      (node (ref "C35") (pin "2") (pintype "passive"))
      (node (ref "C36") (pin "2") (pintype "passive"))
      (node (ref "C37") (pin "2") (pintype "passive"))
      (node (ref "C38") (pin "2") (pintype "passive"))
      (node (ref "C39") (pin "2") (pintype "passive"))
      (node (ref "C4") (pin "2") (pintype "passive"))
      (node (ref "C40") (pin "2") (pintype "passive"))
      (node (ref "C41") (pin "2") (pintype "passive"))
      (node (ref "C42") (pin "2") (pintype "passive"))
      (node (ref "C5") (pin "2") (pintype "passive"))
      (node (ref "C6") (pin "2") (pintype "passive"))
      (node (ref "C7") (pin "2") (pintype "passive"))
      (node (ref "C8") (pin "2") (pintype "passive"))
      (node (ref "C9") (pin "2") (pintype "passive"))
      (node (ref "D1") (pin "1") (pinfunction "VDD_1") (pintype "passive"))
      (node (ref "D10") (pin "1") (pinfunction "VDD_1") (pintype "passive"))
      (node (ref "D11") (pin "1") (pinfunction "VDD_1") (pintype "passive"))
      (node (ref "D12") (pin "1") (pinfunction "VDD_1") (pintype "passive"))
      (node (ref "D13") (pin "1") (pinfunction "VDD_1") (pintype "passive"))
      (node (ref "D14") (pin "1") (pinfunction "VDD_1") (pintype "passive"))
      (node (ref "D15") (pin "1") (pinfunction "VDD_1") (pintype "passive"))
      (node (ref "D16") (pin "1") (pinfunction "VDD_1") (pintype "passive"))
      (node (ref "D17") (pin "1") (pinfunction "VDD_1") (pintype "passive"))
      (node (ref "D18") (pin "1") (pinfunction "VDD_1") (pintype "passive"))
      (node (ref "D19") (pin "1") (pinfunction "VDD_1") (pintype "passive"))
      (node (ref "D2") (pin "1") (pinfunction "VDD_1") (pintype "passive"))
      (node (ref "D20") (pin "1") (pinfunction "VDD_1") (pintype "passive"))
      (node (ref "D21") (pin "1") (pinfunction "VDD_1") (pintype "passive"))
      (node (ref "D22") (pin "1") (pinfunction "VDD_1") (pintype "passive"))
      (node (ref "D23") (pin "1") (pinfunction "VDD_1") (pintype "passive"))
      (node (ref "D24") (pin "1") (pinfunction "VDD_1") (pintype "passive"))
      (node (ref "D25") (pin "1") (pinfunction "VDD_1") (pintype "passive"))
      (node (ref "D26") (pin "1") (pinfunction "VDD_1") (pintype "passive"))
      (node (ref "D27") (pin "1") (pinfunction "VDD_1") (pintype "passive"))
      (node (ref "D28") (pin "1") (pinfunction "VDD_1") (pintype "passive"))
      (node (ref "D29") (pin "1") (pinfunction "VDD_1") (pintype "passive"))
      (node (ref "D3") (pin "1") (pinfunction "VDD_1") (pintype "passive"))
      (node (ref "D30") (pin "1") (pinfunction "VDD_1") (pintype "passive"))
      (node (ref "D31") (pin "1") (pinfunction "VDD_1") (pintype "passive"))
      (node (ref "D32") (pin "1") (pinfunction "VDD_1") (pintype "passive"))
      (node (ref "D33") (pin "1") (pinfunction "VDD_1") (pintype "passive"))
      (node (ref "D34") (pin "1") (pinfunction "VDD_1") (pintype "passive"))
      (node (ref "D35") (pin "1") (pinfunction "VDD_1") (pintype "passive"))
      (node (ref "D36") (pin "1") (pinfunction "VDD_1") (pintype "passive"))
      (node (ref "D37") (pin "1") (pinfunction "VDD_1") (pintype "passive"))
      (node (ref "D38") (pin "1") (pinfunction "VDD_1") (pintype "passive"))
      (node (ref "D39") (pin "1") (pinfunction "VDD_1") (pintype "passive"))
      (node (ref "D4") (pin "1") (pinfunction "VDD_1") (pintype "passive"))
      (node (ref "D40") (pin "1") (pinfunction "VDD_1") (pintype "passive"))
      (node (ref "D41") (pin "1") (pinfunction "VDD_1") (pintype "passive"))
      (node (ref "D5") (pin "1") (pinfunction "VDD_1") (pintype "passive"))
      (node (ref "D6") (pin "1") (pinfunction "VDD_1") (pintype "passive"))
      (node (ref "D7") (pin "1") (pinfunction "VDD_1") (pintype "passive"))
      (node (ref "D8") (pin "1") (pinfunction "VDD_1") (pintype "passive"))
      (node (ref "D9") (pin "1") (pinfunction "VDD_1") (pintype "passive"))
      (node (ref "P1") (pin "1") (pinfunction "1_1") (pintype "passive"))
      (node (ref "R1") (pin "2") (pintype "passive"))
      (node (ref "R2") (pin "2") (pintype "passive"))
      (node (ref "U1") (pin "9") (pinfunction "VDD_9") (pintype "passive"))
      (node (ref "USB1") (pin "1") (pinfunction "VCC_1") (pintype "passive"))
    )
    (net (code "48") (name "unconnected-(D41-DOUT-Pad2)") (class "Default")
      (node (ref "D41") (pin "2") (pinfunction "DOUT_2") (pintype "passive"))
    )
    (net (code "49") (name "unconnected-(U1-PA1{slash}OSCIN-Pad5)") (class "Default")
      (node (ref "U1") (pin "5") (pinfunction "PA1/OSCIN_5") (pintype "passive"))
    )
    (net (code "50") (name "unconnected-(U1-PA2{slash}OSCOUT-Pad6)") (class "Default")
      (node (ref "U1") (pin "6") (pinfunction "PA2/OSCOUT_6") (pintype "passive"))
    )
    (net (code "51") (name "unconnected-(U1-PA3-Pad10)") (class "Default")
      (node (ref "U1") (pin "10") (pinfunction "PA3_10") (pintype "passive"))
    )
    (net (code "52") (name "unconnected-(U1-PB4-Pad12)") (class "Default")
      (node (ref "U1") (pin "12") (pinfunction "PB4_12") (pintype "passive"))
    )
    (net (code "53") (name "unconnected-(U1-PB5-Pad11)") (class "Default")
      (node (ref "U1") (pin "11") (pinfunction "PB5_11") (pintype "passive"))
    )
    (net (code "54") (name "unconnected-(U1-PC3-Pad13)") (class "Default")
      (node (ref "U1") (pin "13") (pinfunction "PC3_13") (pintype "passive"))
    )
    (net (code "55") (name "unconnected-(U1-PC5-Pad15)") (class "Default")
      (node (ref "U1") (pin "15") (pinfunction "PC5_15") (pintype "passive"))
    )
    (net (code "56") (name "unconnected-(U1-PC6-Pad16)") (class "Default")
      (node (ref "U1") (pin "16") (pinfunction "PC6_16") (pintype "passive"))
    )
    (net (code "57") (name "unconnected-(U1-PC7-Pad17)") (class "Default")
      (node (ref "U1") (pin "17") (pinfunction "PC7_17") (pintype "passive"))
    )
    (net (code "58") (name "unconnected-(U1-PD2-Pad19)") (class "Default")
      (node (ref "U1") (pin "19") (pinfunction "PD2_19") (pintype "passive"))
    )
    (net (code "59") (name "unconnected-(U1-PD3-Pad20)") (class "Default")
      (node (ref "U1") (pin "20") (pinfunction "PD3_20") (pintype "passive"))
    )
    (net (code "60") (name "unconnected-(U1-PD4-Pad1)") (class "Default")
      (node (ref "U1") (pin "1") (pinfunction "PD4_1") (pintype "passive"))
    )
    (net (code "61") (name "unconnected-(U1-PD5-Pad2)") (class "Default")
      (node (ref "U1") (pin "2") (pinfunction "PD5_2") (pintype "passive"))
    )
    (net (code "62") (name "unconnected-(USB1-D+-Pad3)") (class "Default")
      (node (ref "USB1") (pin "3") (pinfunction "D+_3") (pintype "passive"))
    )
    (net (code "63") (name "unconnected-(USB1-D--Pad2)") (class "Default")
      (node (ref "USB1") (pin "2") (pinfunction "D-_2") (pintype "passive"))
    )
    (net (code "64") (name "unconnected-(USB1-SHIELD-Pad0)") (class "Default")
      (node (ref "USB1") (pin "0") (pinfunction "SHIELD_0") (pintype "passive"))
    )
  )
)
